# Battery_connector.net
KiCad netlist of a schematic drawn in EAGLE
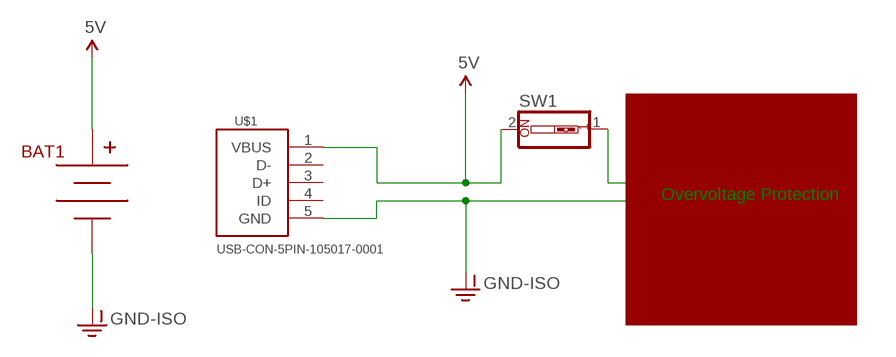
[diagram p0: schematic, sheet 1]

(export (version "E")
  (design (tool "Eeschema 10.0.6"))
  (components
    (comp (ref "BAT1")
      (value "BC9VPC")
      (footprint "eagle-import:BC9VPC")
      (libsource (lib "eagle-import") (part "BC9VPC"))
    )
    (comp (ref "SW1")
      (value "SW_DIP-1")
      (footprint "eagle-import:EDG-01")
      (libsource (lib "eagle-import") (part "SW_DIP-1"))
    )
    (comp (ref "U$1")
      (value "USB-CON-5PIN-105017-0001")
      (footprint "eagle-import:USB-MICRO-MOLEX-105017-0001")
      (libsource (lib "eagle-import") (part "USB-CON-5PIN-105017-0001"))
    )
  )
  (nets
    (net (code "1") (name "5V") (class "Default")
      (node (ref "BAT1") (pin "V+") (pinfunction "V+_V+") (pintype "bidirectional"))
      (node (ref "SW1") (pin "2") (pinfunction "2_2") (pintype "passive"))
      (node (ref "U$1") (pin "1") (pinfunction "VBUS_1") (pintype "power_in"))
    )
    (net (code "2") (name "GND-ISO") (class "Default")
      (node (ref "BAT1") (pin "V-") (pinfunction "V-_V-") (pintype "bidirectional"))
      (node (ref "U$1") (pin "5") (pinfunction "GND_5") (pintype "power_in"))
    )
    (net (code "3") (name "unconnected-(SW1-Pad1)") (class "Default")
      (node (ref "SW1") (pin "1") (pinfunction "1_1") (pintype "passive"))
    )
    (net (code "4") (name "unconnected-(U$1-D+-Pad3)") (class "Default")
      (node (ref "U$1") (pin "3") (pinfunction "D+_3") (pintype "bidirectional"))
    )
    (net (code "5") (name "unconnected-(U$1-D--Pad2)") (class "Default")
      (node (ref "U$1") (pin "2") (pinfunction "D-_2") (pintype "bidirectional"))
    )
    (net (code "6") (name "unconnected-(U$1-ID-Pad4)") (class "Default")
      (node (ref "U$1") (pin "4") (pinfunction "ID_4") (pintype "bidirectional"))
    )
  )
)
